# Sheet1.net
KiCad netlist of a schematic drawn in Altium Designer
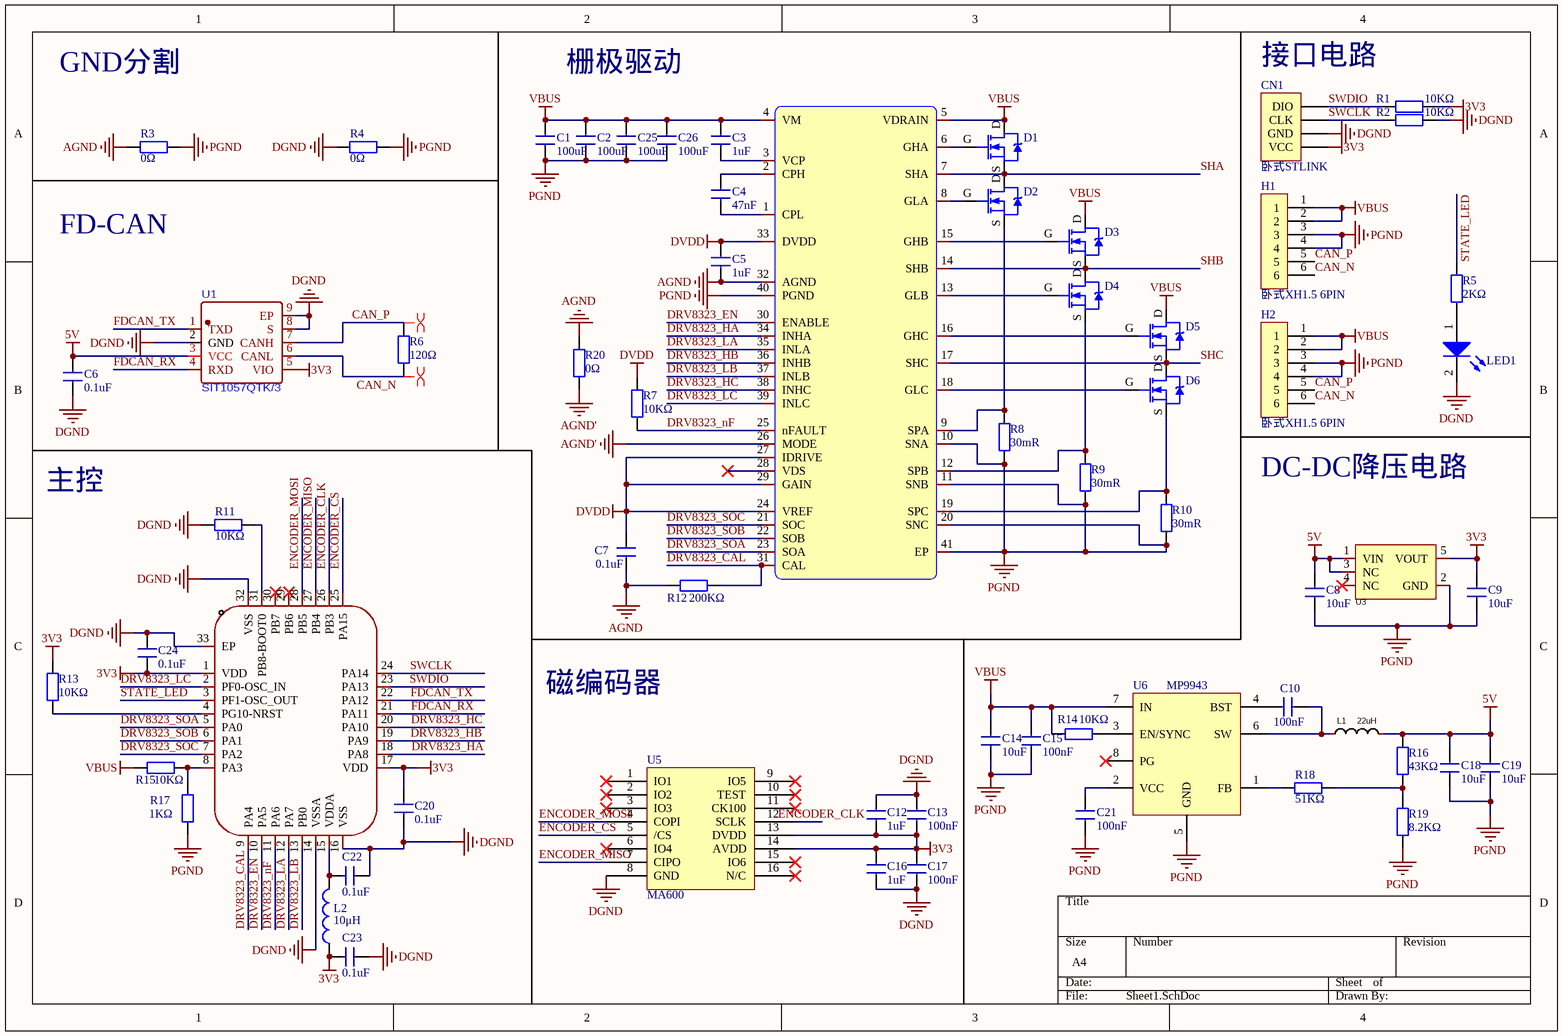
[diagram p0: Sheet1.SchDoc]

(export (version "E")
  (design (tool "Eeschema 10.0.6"))
  (components
    (comp (ref "C1")
      (value "100uF")
      (footprint "1206")
      (description "1210贴片电容")
      (libsource (lib "Integrated_Library1") (part "1210贴片电容"))
    )
    (comp (ref "C2")
      (value "100uF")
      (footprint "1206")
      (description "1210贴片电容")
      (libsource (lib "Integrated_Library1") (part "1210贴片电容"))
    )
    (comp (ref "C3")
      (value "1uF")
      (footprint "c0402")
      (description "贴片电容0402")
      (libsource (lib "Integrated_Library1") (part "0402贴片电容"))
    )
    (comp (ref "C4")
      (value "47nF")
      (footprint "c0402")
      (description "贴片电容0402")
      (libsource (lib "Integrated_Library1") (part "0402贴片电容"))
    )
    (comp (ref "C5")
      (value "1uF")
      (footprint "c0402")
      (description "贴片电容0402")
      (libsource (lib "Integrated_Library1") (part "0402贴片电容"))
    )
    (comp (ref "C6")
      (value "0.1uF")
      (footprint "c0402")
      (description "贴片电容0402")
      (libsource (lib "Integrated_Library1") (part "0402贴片电容"))
    )
    (comp (ref "C7")
      (value "0.1uF")
      (footprint "c0402")
      (description "贴片电容0402")
      (libsource (lib "Integrated_Library1") (part "0402贴片电容"))
    )
    (comp (ref "C8")
      (value "10uF")
      (footprint "c0402")
      (description "贴片电容0402")
      (libsource (lib "Integrated_Library1") (part "0402贴片电容"))
    )
    (comp (ref "C9")
      (value "10uF")
      (footprint "c0402")
      (description "贴片电容0402")
      (libsource (lib "Integrated_Library1") (part "0402贴片电容"))
    )
    (comp (ref "C10")
      (value "100nF")
      (footprint "c0402")
      (description "贴片电容0402")
      (libsource (lib "Integrated_Library1") (part "0402贴片电容"))
    )
    (comp (ref "C12")
      (value "1uF")
      (footprint "C0402")
      (description "贴片电容0402")
      (libsource (lib "Integrated_Library1") (part "0402贴片电容"))
    )
    (comp (ref "C13")
      (value "100nF")
      (footprint "C0402")
      (description "贴片电容0402")
      (libsource (lib "Integrated_Library1") (part "0402贴片电容"))
    )
    (comp (ref "C14")
      (value "10uF")
      (footprint "C0603")
      (description "1210贴片电容")
      (libsource (lib "Integrated_Library1") (part "1210贴片电容"))
    )
    (comp (ref "C15")
      (value "100nF")
      (footprint "c0402")
      (description "贴片电容0402")
      (libsource (lib "Integrated_Library1") (part "0402贴片电容"))
    )
    (comp (ref "C16")
      (value "1uF")
      (footprint "C0402")
      (description "贴片电容0402")
      (libsource (lib "Integrated_Library1") (part "0402贴片电容"))
    )
    (comp (ref "C17")
      (value "100nF")
      (footprint "C0402")
      (description "贴片电容0402")
      (libsource (lib "Integrated_Library1") (part "0402贴片电容"))
    )
    (comp (ref "C18")
      (value "10uF")
      (footprint "C0603")
      (description "1210贴片电容")
      (libsource (lib "Integrated_Library1") (part "1210贴片电容"))
    )
    (comp (ref "C19")
      (value "10uF")
      (footprint "C0603")
      (description "1210贴片电容")
      (libsource (lib "Integrated_Library1") (part "1210贴片电容"))
    )
    (comp (ref "C20")
      (value "0.1uF")
      (footprint "c0402")
      (description "贴片电容0402")
      (libsource (lib "Integrated_Library1") (part "0402贴片电容"))
    )
    (comp (ref "C21")
      (value "100nF")
      (footprint "c0402")
      (description "贴片电容0402")
      (libsource (lib "Integrated_Library1") (part "0402贴片电容"))
    )
    (comp (ref "C22")
      (value "0.1uF")
      (footprint "c0402")
      (description "贴片电容0402")
      (libsource (lib "Integrated_Library1") (part "0402贴片电容"))
    )
    (comp (ref "C23")
      (value "0.1uF")
      (footprint "c0402")
      (description "贴片电容0402")
      (libsource (lib "Integrated_Library1") (part "0402贴片电容"))
    )
    (comp (ref "C24")
      (value "0.1uF")
      (footprint "c0402")
      (description "贴片电容0402")
      (libsource (lib "Integrated_Library1") (part "0402贴片电容"))
    )
    (comp (ref "C25")
      (value "100uF")
      (footprint "1206")
      (description "1210贴片电容")
      (libsource (lib "Integrated_Library1") (part "1210贴片电容"))
    )
    (comp (ref "C26")
      (value "100uF")
      (footprint "1206")
      (description "1210贴片电容")
      (libsource (lib "Integrated_Library1") (part "1210贴片电容"))
    )
    (comp (ref "CN1")
      (value "卧式STLINK")
      (footprint "CONN-SMD_4P-P1.25_GH1.25-4P")
      (libsource (lib "Integrated_Library1") (part "卧式STLINK"))
    )
    (comp (ref "D1")
      (value "NTMFS5C410NL")
      (footprint "DFN-8_L3.0-W3.0-P0.65-BL")
      (description "N沟道MOS管")
      (fields (field (name "PUBLISHER") "Altium Limited"))
      (libsource (lib "En") (part "NTMFS5C410NL"))
    )
    (comp (ref "D2")
      (value "NTMFS5C410NL")
      (footprint "DFN-8_L3.0-W3.0-P0.65-BL")
      (description "N沟道MOS管")
      (fields (field (name "PUBLISHER") "Altium Limited"))
      (libsource (lib "En") (part "NTMFS5C410NL"))
    )
    (comp (ref "D3")
      (value "NTMFS5C410NL")
      (footprint "DFN-8_L3.0-W3.0-P0.65-BL")
      (description "N沟道MOS管")
      (fields (field (name "PUBLISHER") "Altium Limited"))
      (libsource (lib "En") (part "NTMFS5C410NL"))
    )
    (comp (ref "D4")
      (value "NTMFS5C410NL")
      (footprint "DFN-8_L3.0-W3.0-P0.65-BL")
      (description "N沟道MOS管")
      (fields (field (name "PUBLISHER") "Altium Limited"))
      (libsource (lib "En") (part "NTMFS5C410NL"))
    )
    (comp (ref "D5")
      (value "NTMFS5C410NL")
      (footprint "DFN-8_L3.0-W3.0-P0.65-BL")
      (description "N沟道MOS管")
      (fields (field (name "PUBLISHER") "Altium Limited"))
      (libsource (lib "En") (part "NTMFS5C410NL"))
    )
    (comp (ref "D6")
      (value "NTMFS5C410NL")
      (footprint "DFN-8_L3.0-W3.0-P0.65-BL")
      (description "N沟道MOS管")
      (fields (field (name "PUBLISHER") "Altium Limited"))
      (libsource (lib "En") (part "NTMFS5C410NL"))
    )
    (comp (ref "H1")
      (value "卧式XH1.5 6PIN")
      (footprint "CONN-SMD_6P-P1.50_ZX-ZH1.5-6PWT")
      (libsource (lib "En") (part "卧式XH1.5 6PIN"))
    )
    (comp (ref "H2")
      (value "卧式XH1.5 6PIN")
      (footprint "CONN-SMD_6P-P1.50_ZX-ZH1.5-6PWT")
      (libsource (lib "En") (part "卧式XH1.5 6PIN"))
    )
    (comp (ref "L1")
      (value "22uH")
      (footprint "IND-SMD_L2.5-W2.0")
      (description "一体成型屏蔽电感，0530封装，额定电流3A")
      (fields (field (name "MANUFACTURER") "XR(祥如)") (field (name "MANUFACTURER PART") "XR0530-100M"))
      (libsource (lib "Integrated_Library1") (part "0530屏蔽电感"))
    )
    (comp (ref "L2")
      (value "10μH")
      (footprint "L0805")
      (description "0805贴片电感")
      (libsource (lib "Integrated_Library1") (part "0805贴片电感"))
    )
    (comp (ref "LED1")
      (value "LED")
      (footprint "led0805")
      (description "0805贴片LED")
      (libsource (lib "Integrated_Library1") (part "0805贴片LED"))
    )
    (comp (ref "R1")
      (value "10KΩ")
      (footprint "R0402")
      (description "0402贴片电阻")
      (libsource (lib "") (part "0402贴片电阻_2"))
    )
    (comp (ref "R2")
      (value "10KΩ")
      (footprint "R0402")
      (description "0402贴片电阻")
      (libsource (lib "") (part "0402贴片电阻_2"))
    )
    (comp (ref "R3")
      (value "0Ω")
      (footprint "R0402")
      (description "0402贴片电阻")
      (libsource (lib "") (part "0402贴片电阻_2"))
    )
    (comp (ref "R4")
      (value "0Ω")
      (footprint "R0402")
      (description "0402贴片电阻")
      (libsource (lib "") (part "0402贴片电阻_2"))
    )
    (comp (ref "R5")
      (value "2KΩ")
      (footprint "R0402")
      (description "0402贴片电阻")
      (libsource (lib "Integrated_Library1") (part "0402贴片电阻"))
    )
    (comp (ref "R6")
      (value "120Ω")
      (footprint "R0402")
      (description "0402贴片电阻")
      (libsource (lib "") (part "0402贴片电阻_4"))
    )
    (comp (ref "R7")
      (value "10KΩ")
      (footprint "R0402")
      (description "0402贴片电阻")
      (libsource (lib "Integrated_Library1") (part "0402贴片电阻"))
    )
    (comp (ref "R8")
      (value "30mR")
      (footprint "1206")
      (description "2512检流电阻")
      (libsource (lib "Integrated_Library1") (part "2512检流电阻"))
    )
    (comp (ref "R9")
      (value "30mR")
      (footprint "1206")
      (description "2512检流电阻")
      (libsource (lib "Integrated_Library1") (part "2512检流电阻"))
    )
    (comp (ref "R10")
      (value "30mR")
      (footprint "1206")
      (description "2512检流电阻")
      (libsource (lib "Integrated_Library1") (part "2512检流电阻"))
    )
    (comp (ref "R11")
      (value "10KΩ")
      (footprint "R0402")
      (description "0402贴片电阻")
      (libsource (lib "") (part "0402贴片电阻_2"))
    )
    (comp (ref "R12")
      (value "200KΩ")
      (footprint "R0402")
      (description "0402贴片电阻")
      (libsource (lib "") (part "0402贴片电阻_3"))
    )
    (comp (ref "R13")
      (value "10KΩ")
      (footprint "R0402")
      (description "0402贴片电阻")
      (libsource (lib "Integrated_Library1") (part "0402贴片电阻"))
    )
    (comp (ref "R14")
      (value "10KΩ")
      (footprint "R0402")
      (description "0402贴片电阻")
      (libsource (lib "") (part "0402贴片电阻_1"))
    )
    (comp (ref "R15")
      (value "10KΩ")
      (footprint "R0402")
      (description "0402贴片电阻")
      (libsource (lib "") (part "0402贴片电阻_3"))
    )
    (comp (ref "R16")
      (value "43KΩ")
      (footprint "R0402")
      (description "0402贴片电阻")
      (libsource (lib "") (part "0402贴片电阻_5"))
    )
    (comp (ref "R17")
      (value "1KΩ")
      (footprint "R0402")
      (description "0402贴片电阻")
      (libsource (lib "Integrated_Library1") (part "0402贴片电阻"))
    )
    (comp (ref "R18")
      (value "51KΩ")
      (footprint "R0402")
      (description "0402贴片电阻")
      (libsource (lib "") (part "0402贴片电阻_1"))
    )
    (comp (ref "R19")
      (value "8.2KΩ")
      (footprint "R0402")
      (description "0402贴片电阻")
      (libsource (lib "") (part "0402贴片电阻_5"))
    )
    (comp (ref "R20")
      (value "0Ω")
      (footprint "R0402")
      (description "0402贴片电阻")
      (libsource (lib "Integrated_Library1") (part "0402贴片电阻"))
    )
    (comp (ref "U1")
      (value "SIT1057QTK/3")
      (footprint "DFN-8_L3.0-W3.0-P0.65-BL-EP")
      (libsource (lib "En") (part "SIT1057QTK/3"))
    )
    (comp (ref "U2")
      (value "DRV8323HRTAR")
      (footprint "QFN-40_L6.0-W6.0-P0.50-BL-EP4.5")
      (fields (field (name "MANUFACTURER") "TI(德州仪器)"))
      (libsource (lib "Integrated_Library1") (part "DRV8323HRTAR"))
    )
    (comp (ref "U3")
      (value "XC6201P332MR-HXY")
      (footprint "SOT-23-5_L3.0-W1.7-P0.95-LS2.8-BR")
      (description "3.3V LDO")
      (fields (field (name "MANUFACTURER") "HXY MOSFET(华轩阳电子)"))
      (libsource (lib "Integrated_Library1") (part "XC6201P332MR-HXY"))
    )
    (comp (ref "U4")
      (value "STM32G431KBU3")
      (footprint "UFQFPN-32_L5.0-W5.0-P0.50-BL-EP3.5")
      (fields (field (name "MANUFACTURER") "ST(意法半导体)"))
      (libsource (lib "Integrated_Library1") (part "STM32G431KBU3"))
    )
    (comp (ref "U5")
      (value "MA600")
      (footprint "qfn-16-l3.0-w3.0-p0.50-tl-ep1.7")
      (description "磁编码器")
      (libsource (lib "Integrated_Library1") (part "MA600"))
    )
    (comp (ref "U6")
      (value "MP9943")
      (footprint "QFN-8 3x3")
      (libsource (lib "Integrated_Library1") (part "MP9943"))
    )
  )
  (nets
    (net (code "2") (name "/CAN_N") (class "Default")
      (node (ref "H1") (pin "6") (pinfunction "6_6") (pintype "passive"))
      (node (ref "H2") (pin "6") (pinfunction "6_6") (pintype "passive"))
      (node (ref "R6") (pin "1") (pinfunction "1_1") (pintype "passive"))
      (node (ref "U1") (pin "6") (pinfunction "CANL_6") (pintype "passive"))
    )
    (net (code "3") (name "/CAN_P") (class "Default")
      (node (ref "H1") (pin "5") (pinfunction "5_5") (pintype "passive"))
      (node (ref "H2") (pin "5") (pinfunction "5_5") (pintype "passive"))
      (node (ref "R6") (pin "2") (pinfunction "2_2") (pintype "passive"))
      (node (ref "U1") (pin "7") (pinfunction "CANH_7") (pintype "passive"))
    )
    (net (code "4") (name "/DRV8323_CAL") (class "Default")
      (node (ref "R12") (pin "1") (pinfunction "1_1") (pintype "passive"))
      (node (ref "U2") (pin "31") (pinfunction "CAL_31") (pintype "passive"))
      (node (ref "U4") (pin "9") (pinfunction "PA4_9") (pintype "passive"))
    )
    (net (code "5") (name "/DRV8323_EN") (class "Default")
      (node (ref "U2") (pin "30") (pinfunction "ENABLE_30") (pintype "passive"))
      (node (ref "U4") (pin "10") (pinfunction "PA5_10") (pintype "passive"))
    )
    (net (code "6") (name "/DRV8323_HA") (class "Default")
      (node (ref "U2") (pin "34") (pinfunction "INHA_34") (pintype "passive"))
      (node (ref "U4") (pin "18") (pinfunction "PA8_18") (pintype "passive"))
    )
    (net (code "7") (name "/DRV8323_HB") (class "Default")
      (node (ref "U2") (pin "36") (pinfunction "INHB_36") (pintype "passive"))
      (node (ref "U4") (pin "19") (pinfunction "PA9_19") (pintype "passive"))
    )
    (net (code "8") (name "/DRV8323_HC") (class "Default")
      (node (ref "U2") (pin "38") (pinfunction "INHC_38") (pintype "passive"))
      (node (ref "U4") (pin "20") (pinfunction "PA10_20") (pintype "passive"))
    )
    (net (code "9") (name "/DRV8323_LA") (class "Default")
      (node (ref "U2") (pin "35") (pinfunction "INLA_35") (pintype "passive"))
      (node (ref "U4") (pin "12") (pinfunction "PA7_12") (pintype "passive"))
    )
    (net (code "10") (name "/DRV8323_LB") (class "Default")
      (node (ref "U2") (pin "37") (pinfunction "INLB_37") (pintype "passive"))
      (node (ref "U4") (pin "13") (pinfunction "PB0_13") (pintype "passive"))
    )
    (net (code "11") (name "/DRV8323_LC") (class "Default")
      (node (ref "U2") (pin "39") (pinfunction "INLC_39") (pintype "passive"))
      (node (ref "U4") (pin "2") (pinfunction "PF0-OSC_IN_2") (pintype "passive"))
    )
    (net (code "12") (name "/DRV8323_SOA") (class "Default")
      (node (ref "U2") (pin "23") (pinfunction "SOA_23") (pintype "passive"))
      (node (ref "U4") (pin "5") (pinfunction "PA0_5") (pintype "passive"))
    )
    (net (code "13") (name "/DRV8323_SOB") (class "Default")
      (node (ref "U2") (pin "22") (pinfunction "SOB_22") (pintype "passive"))
      (node (ref "U4") (pin "6") (pinfunction "PA1_6") (pintype "passive"))
    )
    (net (code "14") (name "/DRV8323_SOC") (class "Default")
      (node (ref "U2") (pin "21") (pinfunction "SOC_21") (pintype "passive"))
      (node (ref "U4") (pin "7") (pinfunction "PA2_7") (pintype "passive"))
    )
    (net (code "15") (name "/DRV8323_nF") (class "Default")
      (node (ref "R7") (pin "2") (pinfunction "2_2") (pintype "passive"))
      (node (ref "U2") (pin "25") (pinfunction "nFAULT_25") (pintype "passive"))
      (node (ref "U4") (pin "11") (pinfunction "PA6_11") (pintype "passive"))
    )
    (net (code "16") (name "/ENCODER_CLK") (class "Default")
      (node (ref "U4") (pin "26") (pinfunction "PB3_26") (pintype "passive"))
      (node (ref "U5") (pin "12") (pinfunction "SCLK_12") (pintype "passive"))
    )
    (net (code "17") (name "/ENCODER_CS") (class "Default")
      (node (ref "U4") (pin "25") (pinfunction "PA15_25") (pintype "passive"))
      (node (ref "U5") (pin "5") (pinfunction "/CS_5") (pintype "passive"))
    )
    (net (code "18") (name "/ENCODER_MISO") (class "Default")
      (node (ref "U4") (pin "27") (pinfunction "PB4_27") (pintype "passive"))
      (node (ref "U5") (pin "7") (pinfunction "CIPO_7") (pintype "passive"))
    )
    (net (code "19") (name "/ENCODER_MOSI") (class "Default")
      (node (ref "U4") (pin "28") (pinfunction "PB5_28") (pintype "passive"))
      (node (ref "U5") (pin "4") (pinfunction "COPI_4") (pintype "passive"))
    )
    (net (code "20") (name "/FDCAN_RX") (class "Default")
      (node (ref "U1") (pin "4") (pinfunction "RXD_4") (pintype "passive"))
      (node (ref "U4") (pin "21") (pinfunction "PA11_21") (pintype "passive"))
    )
    (net (code "21") (name "/FDCAN_TX") (class "Default")
      (node (ref "U1") (pin "1") (pinfunction "TXD_1") (pintype "passive"))
      (node (ref "U4") (pin "22") (pinfunction "PA12_22") (pintype "passive"))
    )
    (net (code "22") (name "/SHA") (class "Default")
      (node (ref "D1") (pin "S") (pinfunction "S_S") (pintype "passive"))
      (node (ref "D2") (pin "D") (pinfunction "D_D") (pintype "passive"))
      (node (ref "U2") (pin "7") (pinfunction "SHA_7") (pintype "passive"))
    )
    (net (code "23") (name "/SHB") (class "Default")
      (node (ref "D3") (pin "S") (pinfunction "S_S") (pintype "passive"))
      (node (ref "D4") (pin "D") (pinfunction "D_D") (pintype "passive"))
      (node (ref "U2") (pin "14") (pinfunction "SHB_14") (pintype "passive"))
    )
    (net (code "24") (name "/SHC") (class "Default")
      (node (ref "D5") (pin "S") (pinfunction "S_S") (pintype "passive"))
      (node (ref "D6") (pin "D") (pinfunction "D_D") (pintype "passive"))
      (node (ref "U2") (pin "17") (pinfunction "SHC_17") (pintype "passive"))
    )
    (net (code "25") (name "/STATE_LED") (class "Default")
      (node (ref "R5") (pin "1") (pinfunction "1_1") (pintype "passive"))
      (node (ref "U4") (pin "3") (pinfunction "PF1-OSC_OUT_3") (pintype "passive"))
    )
    (net (code "26") (name "/SWCLK") (class "Default")
      (node (ref "CN1") (pin "3") (pinfunction "CLK_3") (pintype "passive"))
      (node (ref "R2") (pin "1") (pinfunction "1_1") (pintype "passive"))
      (node (ref "U4") (pin "24") (pinfunction "PA14_24") (pintype "passive"))
    )
    (net (code "27") (name "/SWDIO") (class "Default")
      (node (ref "CN1") (pin "4") (pinfunction "DIO_4") (pintype "passive"))
      (node (ref "R1") (pin "1") (pinfunction "1_1") (pintype "passive"))
      (node (ref "U4") (pin "23") (pinfunction "PA13_23") (pintype "passive"))
    )
    (net (code "28") (name "3V3") (class "Default")
      (node (ref "C12") (pin "1") (pinfunction "1_1") (pintype "passive"))
      (node (ref "C13") (pin "1") (pinfunction "1_1") (pintype "passive"))
      (node (ref "C16") (pin "2") (pinfunction "2_2") (pintype "passive"))
      (node (ref "C17") (pin "2") (pinfunction "2_2") (pintype "passive"))
      (node (ref "C20") (pin "1") (pinfunction "1_1") (pintype "passive"))
      (node (ref "C23") (pin "2") (pinfunction "2_2") (pintype "passive"))
      (node (ref "C24") (pin "1") (pinfunction "1_1") (pintype "passive"))
      (node (ref "C9") (pin "2") (pinfunction "2_2") (pintype "passive"))
      (node (ref "CN1") (pin "1") (pinfunction "VCC_1") (pintype "passive"))
      (node (ref "L2") (pin "1") (pinfunction "1_1") (pintype "passive"))
      (node (ref "R1") (pin "2") (pinfunction "2_2") (pintype "passive"))
      (node (ref "R13") (pin "1") (pinfunction "1_1") (pintype "passive"))
      (node (ref "U1") (pin "5") (pinfunction "VIO_5") (pintype "passive"))
      (node (ref "U3") (pin "5") (pinfunction "VOUT_5") (pintype "passive"))
      (node (ref "U4") (pin "1") (pinfunction "VDD_1") (pintype "passive"))
      (node (ref "U4") (pin "17") (pinfunction "VDD_17") (pintype "passive"))
      (node (ref "U5") (pin "13") (pinfunction "DVDD_13") (pintype "passive"))
      (node (ref "U5") (pin "14") (pinfunction "AVDD_14") (pintype "passive"))
    )
    (net (code "29") (name "5V") (class "Default")
      (node (ref "C18") (pin "2") (pinfunction "2_2") (pintype "passive"))
      (node (ref "C19") (pin "2") (pinfunction "2_2") (pintype "passive"))
      (node (ref "C6") (pin "2") (pinfunction "2_2") (pintype "passive"))
      (node (ref "C8") (pin "2") (pinfunction "2_2") (pintype "passive"))
      (node (ref "L1") (pin "2") (pinfunction "2_2") (pintype "passive"))
      (node (ref "R16") (pin "2") (pinfunction "2_2") (pintype "passive"))
      (node (ref "U1") (pin "3") (pinfunction "VCC_3") (pintype "passive"))
      (node (ref "U3") (pin "1") (pinfunction "VIN_1") (pintype "passive"))
      (node (ref "U3") (pin "3") (pinfunction "NC_3") (pintype "passive"))
    )
    (net (code "30") (name "AGND") (class "Default")
      (node (ref "C5") (pin "1") (pinfunction "1_1") (pintype "passive"))
      (node (ref "C7") (pin "1") (pinfunction "1_1") (pintype "passive"))
      (node (ref "R12") (pin "2") (pinfunction "2_2") (pintype "passive"))
      (node (ref "R20") (pin "1") (pinfunction "1_1") (pintype "passive"))
      (node (ref "R3") (pin "1") (pinfunction "1_1") (pintype "passive"))
      (node (ref "U2") (pin "32") (pinfunction "AGND_32") (pintype "passive"))
    )
    (net (code "31") (name "AGND'") (class "Default")
      (node (ref "R20") (pin "2") (pinfunction "2_2") (pintype "passive"))
      (node (ref "U2") (pin "26") (pinfunction "MODE_26") (pintype "passive"))
    )
    (net (code "32") (name "DGND") (class "Default")
      (node (ref "C12") (pin "2") (pinfunction "2_2") (pintype "passive"))
      (node (ref "C13") (pin "2") (pinfunction "2_2") (pintype "passive"))
      (node (ref "C16") (pin "1") (pinfunction "1_1") (pintype "passive"))
      (node (ref "C17") (pin "1") (pinfunction "1_1") (pintype "passive"))
      (node (ref "C20") (pin "2") (pinfunction "2_2") (pintype "passive"))
      (node (ref "C22") (pin "1") (pinfunction "1_1") (pintype "passive"))
      (node (ref "C23") (pin "1") (pinfunction "1_1") (pintype "passive"))
      (node (ref "C24") (pin "2") (pinfunction "2_2") (pintype "passive"))
      (node (ref "C6") (pin "1") (pinfunction "1_1") (pintype "passive"))
      (node (ref "CN1") (pin "2") (pinfunction "GND_2") (pintype "passive"))
      (node (ref "LED1") (pin "2") (pinfunction "K_2") (pintype "passive"))
      (node (ref "R11") (pin "1") (pinfunction "1_1") (pintype "passive"))
      (node (ref "R2") (pin "2") (pinfunction "2_2") (pintype "passive"))
      (node (ref "R4") (pin "1") (pinfunction "1_1") (pintype "passive"))
      (node (ref "U1") (pin "2") (pinfunction "GND_2") (pintype "passive"))
      (node (ref "U1") (pin "8") (pinfunction "S_8") (pintype "passive"))
      (node (ref "U1") (pin "9") (pinfunction "EP_9") (pintype "passive"))
      (node (ref "U4") (pin "14") (pinfunction "VSSA_14") (pintype "passive"))
      (node (ref "U4") (pin "16") (pinfunction "VSS_16") (pintype "passive"))
      (node (ref "U4") (pin "32") (pinfunction "VSS_32") (pintype "passive"))
      (node (ref "U4") (pin "33") (pinfunction "EP_33") (pintype "passive"))
      (node (ref "U5") (pin "8") (pinfunction "GND_8") (pintype "passive"))
    )
    (net (code "33") (name "DVDD") (class "Default")
      (node (ref "C5") (pin "2") (pinfunction "2_2") (pintype "passive"))
      (node (ref "C7") (pin "2") (pinfunction "2_2") (pintype "passive"))
      (node (ref "R7") (pin "1") (pinfunction "1_1") (pintype "passive"))
      (node (ref "U2") (pin "24") (pinfunction "VREF_24") (pintype "passive"))
      (node (ref "U2") (pin "27") (pinfunction "IDRIVE_27") (pintype "passive"))
      (node (ref "U2") (pin "29") (pinfunction "GAIN_29") (pintype "passive"))
      (node (ref "U2") (pin "33") (pinfunction "DVDD_33") (pintype "passive"))
    )
    (net (code "34") (name "Net-(LED1-A)") (class "Default")
      (node (ref "LED1") (pin "1") (pinfunction "A_1") (pintype "passive"))
      (node (ref "R5") (pin "2") (pinfunction "2_2") (pintype "passive"))
    )
    (net (code "35") (name "Net-(R16-Pad1)") (class "Default")
      (node (ref "R16") (pin "1") (pinfunction "1_1") (pintype "passive"))
      (node (ref "R18") (pin "2") (pinfunction "2_2") (pintype "passive"))
      (node (ref "R19") (pin "2") (pinfunction "2_2") (pintype "passive"))
    )
    (net (code "36") (name "Net-(U2-CPH)") (class "Default")
      (node (ref "C4") (pin "2") (pinfunction "2_2") (pintype "passive"))
      (node (ref "U2") (pin "2") (pinfunction "CPH_2") (pintype "passive"))
    )
    (net (code "37") (name "Net-(U2-CPL)") (class "Default")
      (node (ref "C4") (pin "1") (pinfunction "1_1") (pintype "passive"))
      (node (ref "U2") (pin "1") (pinfunction "CPL_1") (pintype "passive"))
    )
    (net (code "38") (name "Net-(U2-GHA)") (class "Default")
      (node (ref "D1") (pin "G") (pinfunction "G_G") (pintype "passive"))
      (node (ref "U2") (pin "6") (pinfunction "GHA_6") (pintype "passive"))
    )
    (net (code "39") (name "Net-(U2-GHB)") (class "Default")
      (node (ref "D3") (pin "G") (pinfunction "G_G") (pintype "passive"))
      (node (ref "U2") (pin "15") (pinfunction "GHB_15") (pintype "passive"))
    )
    (net (code "40") (name "Net-(U2-GHC)") (class "Default")
      (node (ref "D5") (pin "G") (pinfunction "G_G") (pintype "passive"))
      (node (ref "U2") (pin "16") (pinfunction "GHC_16") (pintype "passive"))
    )
    (net (code "41") (name "Net-(U2-GLA)") (class "Default")
      (node (ref "D2") (pin "G") (pinfunction "G_G") (pintype "passive"))
      (node (ref "U2") (pin "8") (pinfunction "GLA_8") (pintype "passive"))
    )
    (net (code "42") (name "Net-(U2-GLB)") (class "Default")
      (node (ref "D4") (pin "G") (pinfunction "G_G") (pintype "passive"))
      (node (ref "U2") (pin "13") (pinfunction "GLB_13") (pintype "passive"))
    )
    (net (code "43") (name "Net-(U2-GLC)") (class "Default")
      (node (ref "D6") (pin "G") (pinfunction "G_G") (pintype "passive"))
      (node (ref "U2") (pin "18") (pinfunction "GLC_18") (pintype "passive"))
    )
    (net (code "44") (name "Net-(U2-SPA)") (class "Default")
      (node (ref "D2") (pin "S") (pinfunction "S_S") (pintype "passive"))
      (node (ref "R8") (pin "2") (pinfunction "2_2") (pintype "passive"))
      (node (ref "U2") (pin "9") (pinfunction "SPA_9") (pintype "passive"))
    )
    (net (code "45") (name "Net-(U2-SPB)") (class "Default")
      (node (ref "D4") (pin "S") (pinfunction "S_S") (pintype "passive"))
      (node (ref "R9") (pin "2") (pinfunction "2_2") (pintype "passive"))
      (node (ref "U2") (pin "12") (pinfunction "SPB_12") (pintype "passive"))
    )
    (net (code "46") (name "Net-(U2-SPC)") (class "Default")
      (node (ref "D6") (pin "S") (pinfunction "S_S") (pintype "passive"))
      (node (ref "R10") (pin "2") (pinfunction "2_2") (pintype "passive"))
      (node (ref "U2") (pin "19") (pinfunction "SPC_19") (pintype "passive"))
    )
    (net (code "47") (name "Net-(U2-VCP)") (class "Default")
      (node (ref "C3") (pin "1") (pinfunction "1_1") (pintype "passive"))
      (node (ref "U2") (pin "3") (pinfunction "VCP_3") (pintype "passive"))
    )
    (net (code "48") (name "Net-(U4-PA3)") (class "Default")
      (node (ref "R15") (pin "1") (pinfunction "1_1") (pintype "passive"))
      (node (ref "R17") (pin "1") (pinfunction "1_1") (pintype "passive"))
      (node (ref "U4") (pin "8") (pinfunction "PA3_8") (pintype "passive"))
    )
    (net (code "49") (name "Net-(U4-PB8-BOOT0)") (class "Default")
      (node (ref "R11") (pin "2") (pinfunction "2_2") (pintype "passive"))
      (node (ref "U4") (pin "31") (pinfunction "PB8-BOOT0_31") (pintype "passive"))
    )
    (net (code "50") (name "Net-(U4-PG10-NRST)") (class "Default")
      (node (ref "R13") (pin "2") (pinfunction "2_2") (pintype "passive"))
      (node (ref "U4") (pin "4") (pinfunction "PG10-NRST_4") (pintype "passive"))
    )
    (net (code "51") (name "Net-(U4-VDDA)") (class "Default")
      (node (ref "C22") (pin "2") (pinfunction "2_2") (pintype "passive"))
      (node (ref "L2") (pin "2") (pinfunction "2_2") (pintype "passive"))
      (node (ref "U4") (pin "15") (pinfunction "VDDA_15") (pintype "passive"))
    )
    (net (code "52") (name "Net-(U6-BST)") (class "Default")
      (node (ref "C10") (pin "1") (pinfunction "1_1") (pintype "passive"))
      (node (ref "U6") (pin "4") (pinfunction "BST_4") (pintype "passive"))
    )
    (net (code "53") (name "Net-(U6-EN{slash}SYNC)") (class "Default")
      (node (ref "R14") (pin "2") (pinfunction "2_2") (pintype "passive"))
      (node (ref "U6") (pin "3") (pinfunction "EN/SYNC_3") (pintype "passive"))
    )
    (net (code "54") (name "Net-(U6-FB)") (class "Default")
      (node (ref "R18") (pin "1") (pinfunction "1_1") (pintype "passive"))
      (node (ref "U6") (pin "1") (pinfunction "FB_1") (pintype "passive"))
    )
    (net (code "55") (name "Net-(U6-SW)") (class "Default")
      (node (ref "C10") (pin "2") (pinfunction "2_2") (pintype "passive"))
      (node (ref "L1") (pin "1") (pinfunction "1_1") (pintype "passive"))
      (node (ref "U6") (pin "6") (pinfunction "SW_6") (pintype "passive"))
    )
    (net (code "56") (name "Net-(U6-VCC)") (class "Default")
      (node (ref "C21") (pin "2") (pinfunction "2_2") (pintype "passive"))
      (node (ref "U6") (pin "2") (pinfunction "VCC_2") (pintype "passive"))
    )
    (net (code "57") (name "PGND") (class "Default")
      (node (ref "C1") (pin "1") (pinfunction "1_1") (pintype "passive"))
      (node (ref "C14") (pin "1") (pinfunction "1_1") (pintype "passive"))
      (node (ref "C15") (pin "1") (pinfunction "1_1") (pintype "passive"))
      (node (ref "C18") (pin "1") (pinfunction "1_1") (pintype "passive"))
      (node (ref "C19") (pin "1") (pinfunction "1_1") (pintype "passive"))
      (node (ref "C2") (pin "1") (pinfunction "1_1") (pintype "passive"))
      (node (ref "C21") (pin "1") (pinfunction "1_1") (pintype "passive"))
      (node (ref "C25") (pin "1") (pinfunction "1_1") (pintype "passive"))
      (node (ref "C26") (pin "1") (pinfunction "1_1") (pintype "passive"))
      (node (ref "C8") (pin "1") (pinfunction "1_1") (pintype "passive"))
      (node (ref "C9") (pin "1") (pinfunction "1_1") (pintype "passive"))
      (node (ref "H1") (pin "3") (pinfunction "3_3") (pintype "passive"))
      (node (ref "H1") (pin "4") (pinfunction "4_4") (pintype "passive"))
      (node (ref "H2") (pin "3") (pinfunction "3_3") (pintype "passive"))
      (node (ref "H2") (pin "4") (pinfunction "4_4") (pintype "passive"))
      (node (ref "R10") (pin "1") (pinfunction "1_1") (pintype "passive"))
      (node (ref "R17") (pin "2") (pinfunction "2_2") (pintype "passive"))
      (node (ref "R19") (pin "1") (pinfunction "1_1") (pintype "passive"))
      (node (ref "R3") (pin "2") (pinfunction "2_2") (pintype "passive"))
      (node (ref "R4") (pin "2") (pinfunction "2_2") (pintype "passive"))
      (node (ref "R8") (pin "1") (pinfunction "1_1") (pintype "passive"))
      (node (ref "R9") (pin "1") (pinfunction "1_1") (pintype "passive"))
      (node (ref "U2") (pin "10") (pinfunction "SNA_10") (pintype "passive"))
      (node (ref "U2") (pin "11") (pinfunction "SNB_11") (pintype "passive"))
      (node (ref "U2") (pin "20") (pinfunction "SNC_20") (pintype "passive"))
      (node (ref "U2") (pin "40") (pinfunction "PGND_40") (pintype "passive"))
      (node (ref "U2") (pin "41") (pinfunction "EP_41") (pintype "passive"))
      (node (ref "U3") (pin "2") (pinfunction "GND_2") (pintype "passive"))
      (node (ref "U6") (pin "5") (pinfunction "GND_5") (pintype "passive"))
    )
    (net (code "58") (name "VBUS") (class "Default")
      (node (ref "C1") (pin "2") (pinfunction "2_2") (pintype "passive"))
      (node (ref "C14") (pin "2") (pinfunction "2_2") (pintype "passive"))
      (node (ref "C15") (pin "2") (pinfunction "2_2") (pintype "passive"))
      (node (ref "C2") (pin "2") (pinfunction "2_2") (pintype "passive"))
      (node (ref "C25") (pin "2") (pinfunction "2_2") (pintype "passive"))
      (node (ref "C26") (pin "2") (pinfunction "2_2") (pintype "passive"))
      (node (ref "C3") (pin "2") (pinfunction "2_2") (pintype "passive"))
      (node (ref "D1") (pin "D") (pinfunction "D_D") (pintype "passive"))
      (node (ref "D3") (pin "D") (pinfunction "D_D") (pintype "passive"))
      (node (ref "D5") (pin "D") (pinfunction "D_D") (pintype "passive"))
      (node (ref "H1") (pin "1") (pinfunction "1_1") (pintype "passive"))
      (node (ref "H1") (pin "2") (pinfunction "2_2") (pintype "passive"))
      (node (ref "H2") (pin "1") (pinfunction "1_1") (pintype "passive"))
      (node (ref "H2") (pin "2") (pinfunction "2_2") (pintype "passive"))
      (node (ref "R14") (pin "1") (pinfunction "1_1") (pintype "passive"))
      (node (ref "R15") (pin "2") (pinfunction "2_2") (pintype "passive"))
      (node (ref "U2") (pin "4") (pinfunction "VM_4") (pintype "passive"))
      (node (ref "U2") (pin "5") (pinfunction "VDRAIN_5") (pintype "passive"))
      (node (ref "U6") (pin "7") (pinfunction "IN_7") (pintype "passive"))
    )
    (net (code "59") (name "unconnected-(U2-VDS-Pad28)") (class "Default")
      (node (ref "U2") (pin "28") (pinfunction "VDS_28") (pintype "passive+no_connect"))
    )
    (net (code "60") (name "unconnected-(U3-NC-Pad4)") (class "Default")
      (node (ref "U3") (pin "4") (pinfunction "NC_4") (pintype "passive+no_connect"))
    )
    (net (code "61") (name "unconnected-(U4-PB6-Pad29)") (class "Default")
      (node (ref "U4") (pin "29") (pinfunction "PB6_29") (pintype "passive+no_connect"))
    )
    (net (code "62") (name "unconnected-(U4-PB7-Pad30)") (class "Default")
      (node (ref "U4") (pin "30") (pinfunction "PB7_30") (pintype "passive+no_connect"))
    )
    (net (code "63") (name "unconnected-(U5-CK100-Pad11)") (class "Default")
      (node (ref "U5") (pin "11") (pinfunction "CK100_11") (pintype "passive+no_connect"))
    )
    (net (code "64") (name "unconnected-(U5-IO1-Pad1)") (class "Default")
      (node (ref "U5") (pin "1") (pinfunction "IO1_1") (pintype "passive+no_connect"))
    )
    (net (code "65") (name "unconnected-(U5-IO2-Pad2)") (class "Default")
      (node (ref "U5") (pin "2") (pinfunction "IO2_2") (pintype "passive+no_connect"))
    )
    (net (code "66") (name "unconnected-(U5-IO3-Pad3)") (class "Default")
      (node (ref "U5") (pin "3") (pinfunction "IO3_3") (pintype "passive+no_connect"))
    )
    (net (code "67") (name "unconnected-(U5-IO4-Pad6)") (class "Default")
      (node (ref "U5") (pin "6") (pinfunction "IO4_6") (pintype "passive+no_connect"))
    )
    (net (code "68") (name "unconnected-(U5-IO5-Pad9)") (class "Default")
      (node (ref "U5") (pin "9") (pinfunction "IO5_9") (pintype "passive+no_connect"))
    )
    (net (code "69") (name "unconnected-(U5-IO6-Pad15)") (class "Default")
      (node (ref "U5") (pin "15") (pinfunction "IO6_15") (pintype "passive+no_connect"))
    )
    (net (code "70") (name "unconnected-(U5-N{slash}C-Pad16)") (class "Default")
      (node (ref "U5") (pin "16") (pinfunction "N/C_16") (pintype "passive+no_connect"))
    )
    (net (code "71") (name "unconnected-(U5-TEST-Pad10)") (class "Default")
      (node (ref "U5") (pin "10") (pinfunction "TEST_10") (pintype "passive+no_connect"))
    )
    (net (code "72") (name "unconnected-(U6-PG-Pad8)") (class "Default")
      (node (ref "U6") (pin "8") (pinfunction "PG_8") (pintype "passive+no_connect"))
    )
  )
)
